# musIR-tiny-mk-1_0_1.net
KiCad netlist of a schematic drawn in EAGLE
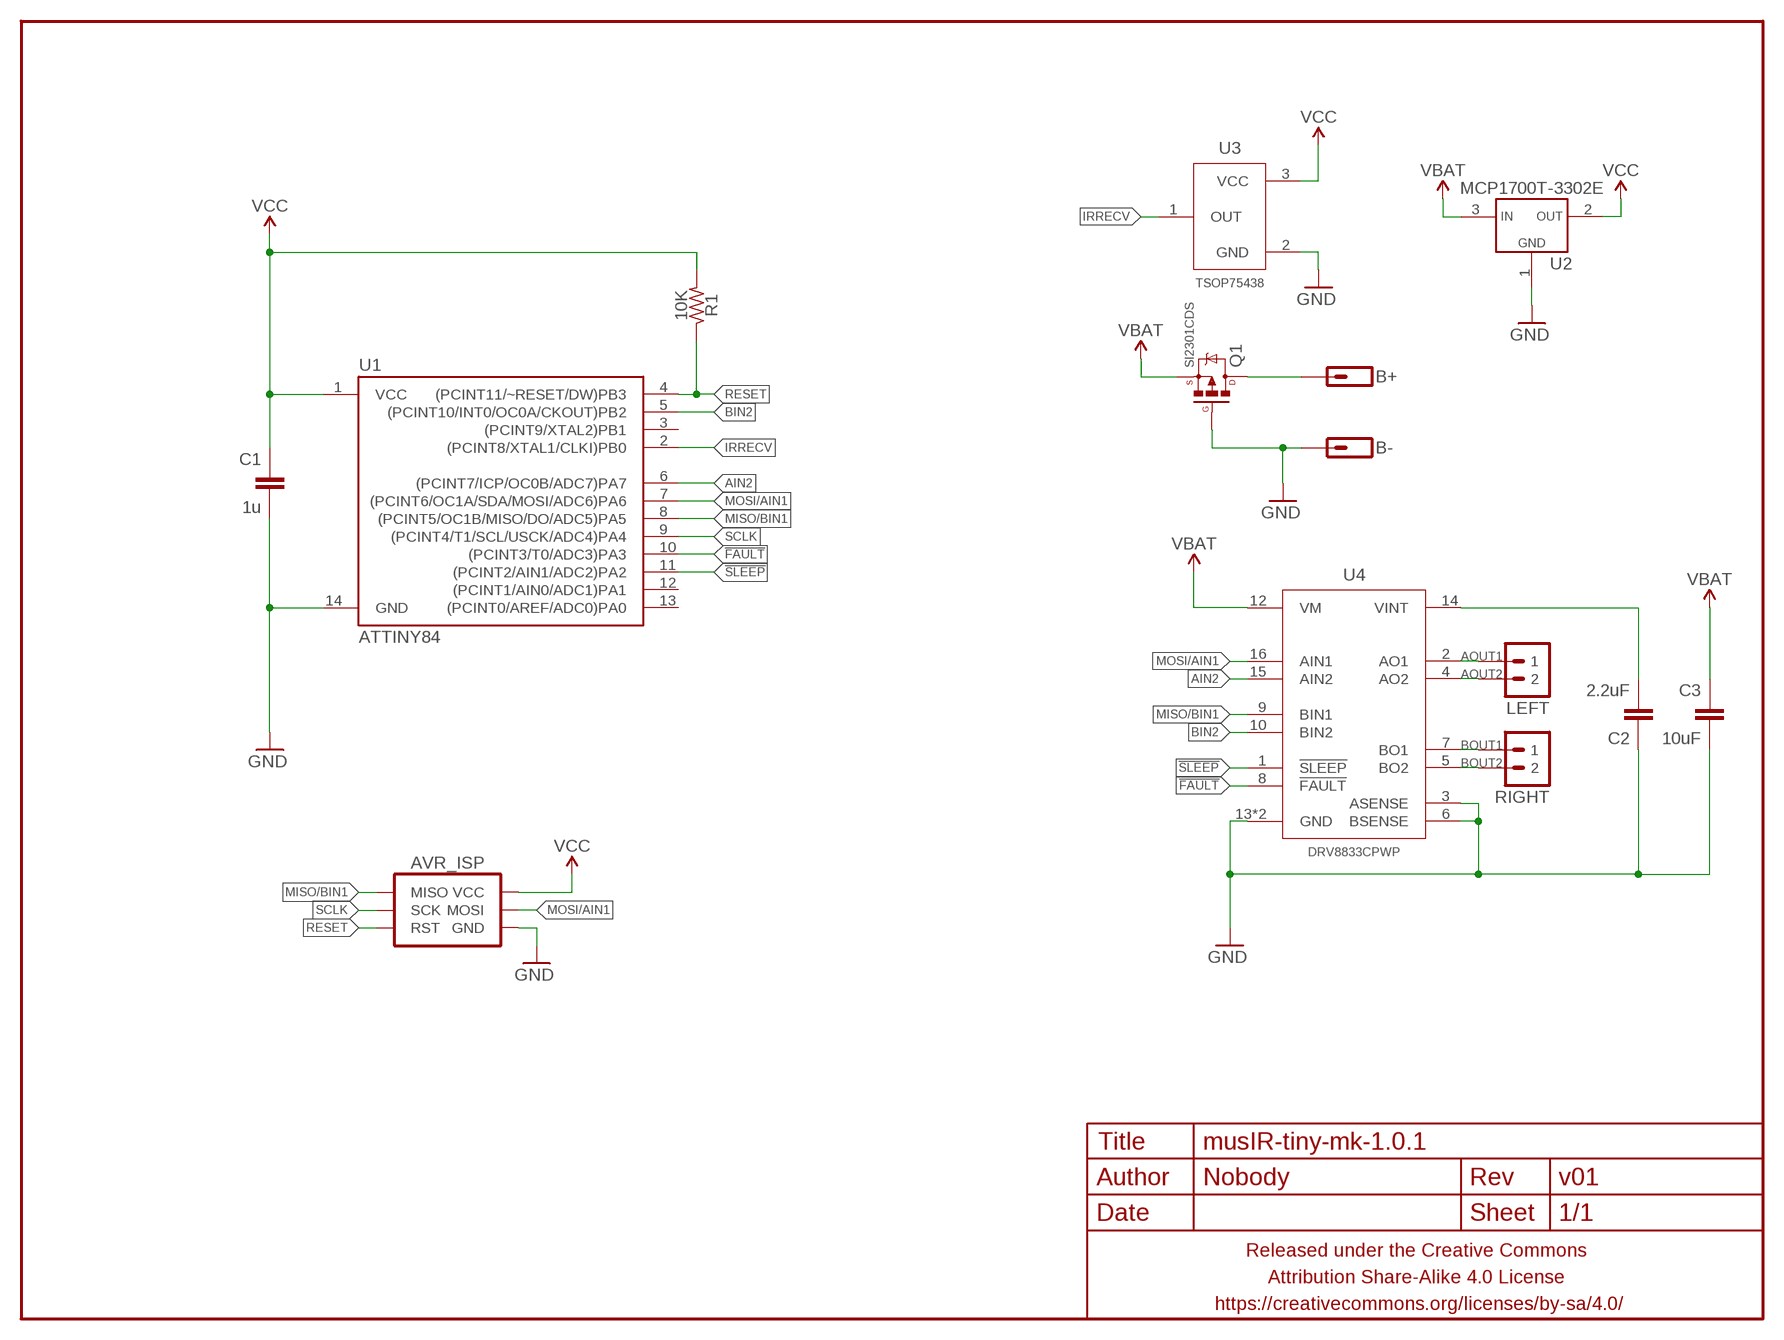
[diagram p0: schematic, sheet 1]

(export (version "E")
  (design (tool "Eeschema 10.0.6"))
  (components
    (comp (ref "AVR_ISP")
      (value "AVR_SPI_PRG_6TESTPOINTS")
      (footprint "eagle-import:2X3_TEST_POINTS")
      (libsource (lib "eagle-import") (part "AVR_SPI_PRG_6TESTPOINTS"))
    )
    (comp (ref "B+")
      (value "M01PTH")
      (footprint "eagle-import:1X01")
      (libsource (lib "eagle-import") (part "M01PTH"))
    )
    (comp (ref "B-")
      (value "M01PTH")
      (footprint "eagle-import:1X01")
      (libsource (lib "eagle-import") (part "M01PTH"))
    )
    (comp (ref "C1")
      (value "1u")
      (footprint "eagle-import:C0603-TIGHTER")
      (libsource (lib "eagle-import") (part "CAPACITOR-CERAMICC0603-TIGHTER"))
    )
    (comp (ref "C2")
      (value "2.2uF")
      (footprint "eagle-import:C0603-TIGHTER")
      (libsource (lib "eagle-import") (part "CAPACITOR-CERAMICC0603-TIGHTER"))
    )
    (comp (ref "C3")
      (value "10uF")
      (footprint "eagle-import:C0805-TIGHTER")
      (libsource (lib "eagle-import") (part "CAPACITOR-CERAMICC0805-TIGHTER"))
    )
    (comp (ref "FRAME1")
      (value "FRAME-LETTERNO_PACKAGE")
      (footprint "eagle-import:DUMMY")
      (fields (field (name "DESIGNER") "Nobody"))
      (libsource (lib "eagle-import") (part "FRAME-LETTERNO_PACKAGE"))
    )
    (comp (ref "LEFT")
      (value "M02PTH-CENTERED")
      (footprint "eagle-import:1X02-CENTER")
      (libsource (lib "eagle-import") (part "M02PTH-CENTERED"))
    )
    (comp (ref "Q1")
      (value "SI2301CDS")
      (footprint "eagle-import:SOT23")
      (libsource (lib "eagle-import") (part "MOSFET-PCHANNELSOT-23"))
    )
    (comp (ref "R1")
      (value "10K")
      (footprint "eagle-import:R0402")
      (libsource (lib "eagle-import") (part "RESISTORR0402"))
    )
    (comp (ref "RIGHT")
      (value "M02PTH-CENTERED")
      (footprint "eagle-import:1X02-CENTER")
      (libsource (lib "eagle-import") (part "M02PTH-CENTERED"))
    )
    (comp (ref "U1")
      (value "ATTINY84")
      (footprint "eagle-import:SO14")
      (libsource (lib "eagle-import") (part "ATTINY84"))
    )
    (comp (ref "U2")
      (value "MCP1700T-3302E")
      (footprint "eagle-import:SOT23-3")
      (libsource (lib "eagle-import") (part "MCP1700SOT-23-3"))
    )
    (comp (ref "U3")
      (value "TSOP75438")
      (footprint "eagle-import:TSOP38238")
      (libsource (lib "eagle-import") (part "TSOP382__/4__"))
    )
    (comp (ref "U4")
      (value "DRV8833CPWP")
      (footprint "eagle-import:TSSOP-16-PAD")
      (libsource (lib "eagle-import") (part "DRV8833CPWP"))
    )
  )
  (nets
    (net (code "1") (name "/AOUT1") (class "Default")
      (node (ref "LEFT") (pin "1") (pinfunction "1_1") (pintype "passive"))
      (node (ref "U4") (pin "2") (pinfunction "AO1_2") (pintype "bidirectional"))
    )
    (net (code "2") (name "/AOUT2") (class "Default")
      (node (ref "LEFT") (pin "2") (pinfunction "2_2") (pintype "passive"))
      (node (ref "U4") (pin "4") (pinfunction "AO2_4") (pintype "bidirectional"))
    )
    (net (code "3") (name "/BOUT1") (class "Default")
      (node (ref "RIGHT") (pin "1") (pinfunction "1_1") (pintype "passive"))
      (node (ref "U4") (pin "7") (pinfunction "BO1_7") (pintype "bidirectional"))
    )
    (net (code "4") (name "/BOUT2") (class "Default")
      (node (ref "RIGHT") (pin "2") (pinfunction "2_2") (pintype "passive"))
      (node (ref "U4") (pin "5") (pinfunction "BO2_5") (pintype "bidirectional"))
    )
    (net (code "5") (name "/~{FAULT}") (class "Default")
      (node (ref "U1") (pin "10") (pinfunction "(PCINT3/T0/ADC3)PA3_10") (pintype "bidirectional"))
      (node (ref "U4") (pin "8") (pinfunction "~{FAULT}_8") (pintype "output"))
    )
    (net (code "6") (name "/~{SLEEP}") (class "Default")
      (node (ref "U1") (pin "11") (pinfunction "(PCINT2/AIN1/ADC2)PA2_11") (pintype "bidirectional"))
      (node (ref "U4") (pin "1") (pinfunction "~{SLEEP}_1") (pintype "input"))
    )
    (net (code "7") (name "AIN2") (class "Default")
      (node (ref "U1") (pin "6") (pinfunction "(PCINT7/ICP/OC0B/ADC7)PA7_6") (pintype "bidirectional"))
      (node (ref "U4") (pin "15") (pinfunction "AIN2_15") (pintype "input"))
    )
    (net (code "8") (name "BIN2") (class "Default")
      (node (ref "U1") (pin "5") (pinfunction "(PCINT10/INT0/OC0A/CKOUT)PB2_5") (pintype "bidirectional"))
      (node (ref "U4") (pin "10") (pinfunction "BIN2_10") (pintype "input"))
    )
    (net (code "9") (name "GND") (class "Default")
      (node (ref "AVR_ISP") (pin "6") (pinfunction "GND_6") (pintype "passive"))
      (node (ref "B-") (pin "1") (pinfunction "1_1") (pintype "passive"))
      (node (ref "C1") (pin "2") (pinfunction "2_2") (pintype "passive"))
      (node (ref "C2") (pin "1") (pinfunction "1_1") (pintype "passive"))
      (node (ref "C3") (pin "2") (pinfunction "2_2") (pintype "passive"))
      (node (ref "Q1") (pin "1") (pinfunction "G_1") (pintype "passive"))
      (node (ref "U1") (pin "14") (pinfunction "GND_14") (pintype "bidirectional"))
      (node (ref "U2") (pin "1") (pinfunction "GND_1") (pintype "bidirectional"))
      (node (ref "U3") (pin "2") (pinfunction "GND_2") (pintype "bidirectional"))
      (node (ref "U4") (pin "13") (pinfunction "GND_13") (pintype "bidirectional"))
      (node (ref "U4") (pin "3") (pinfunction "ASENSE_3") (pintype "bidirectional"))
      (node (ref "U4") (pin "6") (pinfunction "BSENSE_6") (pintype "bidirectional"))
      (node (ref "U4") (pin "PAD") (pinfunction "GND_PAD") (pintype "bidirectional"))
    )
    (net (code "10") (name "IRRECV") (class "Default")
      (node (ref "U1") (pin "2") (pinfunction "(PCINT8/XTAL1/CLKI)PB0_2") (pintype "bidirectional"))
      (node (ref "U3") (pin "1") (pinfunction "OUT_1") (pintype "bidirectional"))
    )
    (net (code "11") (name "MISO{slash}BIN1") (class "Default")
      (node (ref "AVR_ISP") (pin "1") (pinfunction "MISO_1") (pintype "passive"))
      (node (ref "U1") (pin "8") (pinfunction "(PCINT5/OC1B/MISO/DO/ADC5)PA5_8") (pintype "bidirectional"))
      (node (ref "U4") (pin "9") (pinfunction "BIN1_9") (pintype "input"))
    )
    (net (code "12") (name "MOSI{slash}AIN1") (class "Default")
      (node (ref "AVR_ISP") (pin "4") (pinfunction "MOSI_4") (pintype "passive"))
      (node (ref "U1") (pin "7") (pinfunction "(PCINT6/OC1A/SDA/MOSI/ADC6)PA6_7") (pintype "bidirectional"))
      (node (ref "U4") (pin "16") (pinfunction "AIN1_16") (pintype "input"))
    )
    (net (code "13") (name "Net-(Q1-D)") (class "Default")
      (node (ref "B+") (pin "1") (pinfunction "1_1") (pintype "passive"))
      (node (ref "Q1") (pin "3") (pinfunction "D_3") (pintype "passive"))
    )
    (net (code "14") (name "Net-(U4-VINT)") (class "Default")
      (node (ref "C2") (pin "2") (pinfunction "2_2") (pintype "passive"))
      (node (ref "U4") (pin "14") (pinfunction "VINT_14") (pintype "bidirectional"))
    )
    (net (code "15") (name "RESET") (class "Default")
      (node (ref "AVR_ISP") (pin "5") (pinfunction "RST_5") (pintype "passive"))
      (node (ref "R1") (pin "1") (pinfunction "1_1") (pintype "passive"))
      (node (ref "U1") (pin "4") (pinfunction "(PCINT11/~{RESET/DW})PB3_4") (pintype "bidirectional"))
    )
    (net (code "16") (name "SCLK") (class "Default")
      (node (ref "AVR_ISP") (pin "3") (pinfunction "SCK_3") (pintype "passive"))
      (node (ref "U1") (pin "9") (pinfunction "(PCINT4/T1/SCL/USCK/ADC4)PA4_9") (pintype "bidirectional"))
    )
    (net (code "17") (name "VBAT") (class "Default")
      (node (ref "C3") (pin "1") (pinfunction "1_1") (pintype "passive"))
      (node (ref "Q1") (pin "2") (pinfunction "S_2") (pintype "passive"))
      (node (ref "U2") (pin "3") (pinfunction "VIN_3") (pintype "bidirectional"))
      (node (ref "U4") (pin "12") (pinfunction "VM_12") (pintype "bidirectional"))
    )
    (net (code "18") (name "VCC") (class "Default")
      (node (ref "AVR_ISP") (pin "2") (pinfunction "VCC_2") (pintype "passive"))
      (node (ref "C1") (pin "1") (pinfunction "1_1") (pintype "passive"))
      (node (ref "R1") (pin "2") (pinfunction "2_2") (pintype "passive"))
      (node (ref "U1") (pin "1") (pinfunction "VCC_1") (pintype "bidirectional"))
      (node (ref "U2") (pin "2") (pinfunction "VOUT_2") (pintype "bidirectional"))
      (node (ref "U3") (pin "3") (pinfunction "VCC_3") (pintype "bidirectional"))
    )
    (net (code "19") (name "unconnected-(U1-(PCINT0{slash}AREF{slash}ADC0)PA0-Pad13)") (class "Default")
      (node (ref "U1") (pin "13") (pinfunction "(PCINT0/AREF/ADC0)PA0_13") (pintype "bidirectional"))
    )
    (net (code "20") (name "unconnected-(U1-(PCINT1{slash}AIN0{slash}ADC1)PA1-Pad12)") (class "Default")
      (node (ref "U1") (pin "12") (pinfunction "(PCINT1/AIN0/ADC1)PA1_12") (pintype "bidirectional"))
    )
    (net (code "21") (name "unconnected-(U1-(PCINT9{slash}XTAL2)PB1-Pad3)") (class "Default")
      (node (ref "U1") (pin "3") (pinfunction "(PCINT9/XTAL2)PB1_3") (pintype "bidirectional"))
    )
  )
)
